# Power.net
KiCad netlist of a schematic drawn in Altium Designer
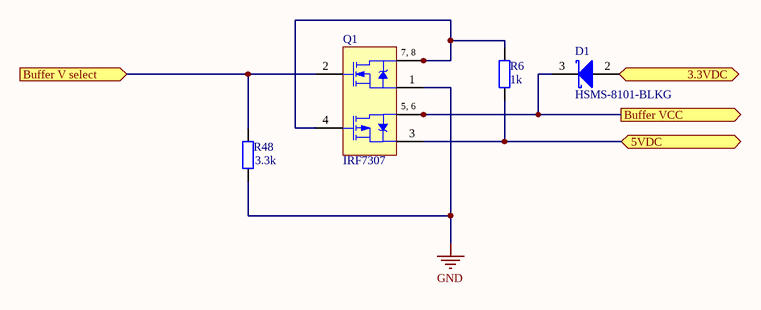
[diagram p0: Power.SchDoc]

(export (version "E")
  (design (tool "Eeschema 10.0.6"))
  (components
    (comp (ref "D1")
      (value "HSMS-8101-BLKG")
      (footprint "SOT-23_N")
      (description "Schottky Diode")
      (fields (field (name "PUBLISHER") "Altium Limited"))
      (libsource (lib "Miscellaneous Devices") (part "D Schottky"))
    )
    (comp (ref "Q1")
      (value "IRF7307")
      (footprint "SO-8_N")
      (description "HEXFET Power MOSFET")
      (fields (field (name "PUBLISHER") "Altium Limited"))
      (libsource (lib "IR Discrete MOSFET - Power") (part "IRF7307"))
    )
    (comp (ref "R6")
      (value "1k")
      (footprint "R_0603")
      (description "Resistor")
      (fields (field (name "Comment") "Res") (field (name "PUBLISHER") "Altium Limited"))
      (libsource (lib "AX_Altium_v2.3") (part "Res2"))
    )
    (comp (ref "R48")
      (value "3.3k")
      (footprint "R_0603")
      (description "Resistor")
      (fields (field (name "Comment") "Res") (field (name "PUBLISHER") "Altium Limited"))
      (libsource (lib "") (part "Res2_1"))
    )
  )
  (nets
    (net (code "1") (name "/3.3VDC") (class "Default")
      (node (ref "D1") (pin "2") (pinfunction "A_2") (pintype "passive"))
    )
    (net (code "2") (name "/5VDC") (class "Default")
      (node (ref "Q1") (pin "3") (pinfunction "S2_3") (pintype "passive"))
      (node (ref "R6") (pin "2") (pinfunction "2_2") (pintype "passive"))
    )
    (net (code "3") (name "/Buffer V select") (class "Default")
      (node (ref "Q1") (pin "2") (pinfunction "G1_2") (pintype "passive"))
      (node (ref "R48") (pin "2") (pinfunction "2_2") (pintype "passive"))
    )
    (net (code "4") (name "/Buffer VCC") (class "Default")
      (node (ref "D1") (pin "3") (pinfunction "K_3") (pintype "passive"))
      (node (ref "Q1") (pin "5") (pinfunction "D2_5") (pintype "passive"))
      (node (ref "Q1") (pin "6") (pinfunction "D2_6") (pintype "passive"))
    )
    (net (code "5") (name "GND") (class "Default")
      (node (ref "Q1") (pin "1") (pinfunction "S1_1") (pintype "passive"))
      (node (ref "R48") (pin "1") (pinfunction "1_1") (pintype "passive"))
    )
    (net (code "6") (name "Net-(Q1-G2)") (class "Default")
      (node (ref "Q1") (pin "4") (pinfunction "G2_4") (pintype "passive"))
      (node (ref "Q1") (pin "7") (pinfunction "D1_7") (pintype "passive"))
      (node (ref "Q1") (pin "8") (pinfunction "D1_8") (pintype "passive"))
      (node (ref "R6") (pin "1") (pinfunction "1_1") (pintype "passive"))
    )
  )
)
